# PowerSupply.net
KiCad netlist of a schematic drawn in Altium Designer
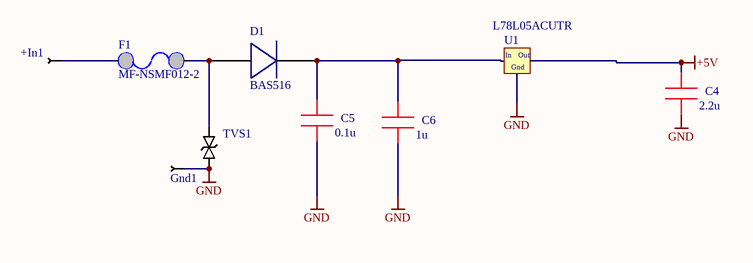
[diagram p0: PowerSupply.SchDoc]

(export (version "E")
  (design (tool "Eeschema 10.0.6"))
  (components
    (comp (ref "+In1")
      (value "PIN_Wire")
      (footprint "PIN_wire")
      (description "pin")
      (libsource (lib "kontr") (part "PIN_Wire"))
    )
    (comp (ref "C4")
      (value "2.2u")
      (footprint "0603")
      (description "GRM188R61E225KA12D")
      (libsource (lib "kontr") (part "Capasitor 0805"))
    )
    (comp (ref "C5")
      (value "0.1u")
      (footprint "0805")
      (description "CC0805KRX7R9BB104")
      (libsource (lib "kontr") (part "Capasitor 0805"))
    )
    (comp (ref "C6")
      (value "1u")
      (footprint "0603")
      (description "CC0603KRX7R9BB105")
      (libsource (lib "kontr") (part "Capasitor 0805"))
    )
    (comp (ref "D1") (value "BAS516") (footprint "SOD523") (libsource (lib "kontr") (part "BAS516")))
    (comp (ref "F1")
      (value "MF-NSMF012-2")
      (footprint "FUSE MF12")
      (libsource (lib "kontr") (part "Fuse PTS"))
    )
    (comp (ref "Gnd1")
      (value "PIN_Wire")
      (footprint "PIN_wire")
      (description "pin")
      (libsource (lib "kontr") (part "PIN_Wire"))
    )
    (comp (ref "TVS1")
      (value "SMAJ5.0CA")
      (footprint "DO-214AC")
      (description "SMAJ30CA")
      (libsource (lib "kontr") (part "SMAJ5.0CA"))
    )
    (comp (ref "U1")
      (value "L78L05ACUTR")
      (description "SOT-89")
      (libsource (lib "kontr") (part "LDO_SOT89"))
    )
  )
  (nets
    (net (code "1") (name "+5V") (class "Default")
      (node (ref "C4") (pin "2") (pinfunction "2_2") (pintype "passive"))
      (node (ref "U1") (pin "1") (pinfunction "OUT_1") (pintype "passive"))
    )
    (net (code "2") (name "GND") (class "Default")
      (node (ref "C4") (pin "1") (pinfunction "1_1") (pintype "passive"))
      (node (ref "C5") (pin "1") (pinfunction "1_1") (pintype "passive"))
      (node (ref "C6") (pin "1") (pinfunction "1_1") (pintype "passive"))
      (node (ref "Gnd1") (pin "0") (pinfunction "0_0") (pintype "passive"))
      (node (ref "TVS1") (pin "1") (pinfunction "1_1") (pintype "passive"))
      (node (ref "U1") (pin "2") (pinfunction "GND_2") (pintype "passive"))
    )
    (net (code "3") (name "Net-(+In1-Pad0)") (class "Default")
      (node (ref "+In1") (pin "0") (pinfunction "0_0") (pintype "passive"))
      (node (ref "F1") (pin "1") (pinfunction "1_1") (pintype "passive"))
    )
    (net (code "4") (name "Net-(D1-Pad2)") (class "Default")
      (node (ref "D1") (pin "2") (pinfunction "2_2") (pintype "passive"))
      (node (ref "F1") (pin "0") (pinfunction "0_0") (pintype "passive"))
      (node (ref "TVS1") (pin "2") (pinfunction "2_2") (pintype "passive"))
    )
    (net (code "5") (name "Net-(U1-IN)") (class "Default")
      (node (ref "C5") (pin "2") (pinfunction "2_2") (pintype "passive"))
      (node (ref "C6") (pin "2") (pinfunction "2_2") (pintype "passive"))
      (node (ref "D1") (pin "1") (pinfunction "1_1") (pintype "passive"))
      (node (ref "U1") (pin "3") (pinfunction "IN_3") (pintype "passive"))
    )
  )
)
